# MCPGrundplatte16xOutput.net
KiCad netlist of a schematic drawn in EAGLE
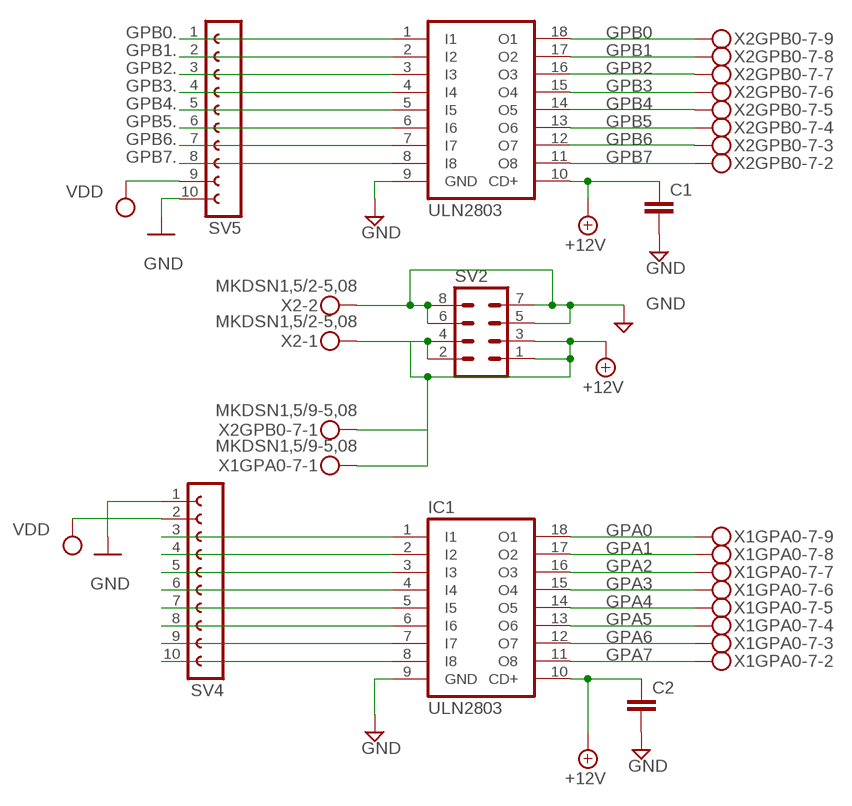
[diagram p0: schematic, sheet 1]

(export (version "E")
  (design (tool "Eeschema 10.0.6"))
  (components
    (comp (ref "C1")
      (value "C-EU025-024X044")
      (footprint "eagle-import:C025-024X044")
      (libsource (lib "eagle-import") (part "C-EU025-024X044"))
    )
    (comp (ref "C2")
      (value "C-EU025-024X044")
      (footprint "eagle-import:C025-024X044")
      (libsource (lib "eagle-import") (part "C-EU025-024X044"))
    )
    (comp (ref "IC1")
      (value "ULN2803")
      (footprint "eagle-import:DIL18")
      (libsource (lib "eagle-import") (part "ULN2803A"))
    )
    (comp (ref "IC4")
      (value "ULN2803")
      (footprint "eagle-import:DIL18")
      (libsource (lib "eagle-import") (part "ULN2803A"))
    )
    (comp (ref "SV2")
      (value "MA04-2")
      (footprint "eagle-import:MA04-2")
      (libsource (lib "eagle-import") (part "MA04-2"))
    )
    (comp (ref "SV4")
      (value "FE10-1")
      (footprint "eagle-import:FE10")
      (libsource (lib "eagle-import") (part "FE10-1"))
    )
    (comp (ref "SV5")
      (value "FE10-1")
      (footprint "eagle-import:FE10")
      (libsource (lib "eagle-import") (part "FE10-1"))
    )
    (comp (ref "X1GPA0-7")
      (value "MKDSN1,5/9-5,08")
      (footprint "eagle-import:MKDSN1,5_9-5,08")
      (libsource (lib "eagle-import") (part "MKDSN1,5/9-5,08"))
    )
    (comp (ref "X2")
      (value "MKDSN1,5/2-5,08")
      (footprint "eagle-import:MKDSN1,5_2-5,08")
      (libsource (lib "eagle-import") (part "MKDSN1,5/2-5,08"))
    )
    (comp (ref "X2GPB0-7")
      (value "MKDSN1,5/9-5,08")
      (footprint "eagle-import:MKDSN1,5_9-5,08")
      (libsource (lib "eagle-import") (part "MKDSN1,5/9-5,08"))
    )
  )
  (nets
    (net (code "1") (name "+12V") (class "Default")
      (node (ref "C1") (pin "1") (pinfunction "1_1") (pintype "passive"))
      (node (ref "C2") (pin "1") (pinfunction "1_1") (pintype "passive"))
      (node (ref "IC1") (pin "10") (pinfunction "CD+_10") (pintype "passive"))
      (node (ref "IC4") (pin "10") (pinfunction "CD+_10") (pintype "passive"))
      (node (ref "SV2") (pin "1") (pinfunction "1_1") (pintype "passive"))
      (node (ref "SV2") (pin "2") (pinfunction "2_2") (pintype "passive"))
      (node (ref "SV2") (pin "3") (pinfunction "3_3") (pintype "passive"))
      (node (ref "SV2") (pin "4") (pinfunction "4_4") (pintype "passive"))
      (node (ref "X1GPA0-7") (pin "1") (pinfunction "KL_1") (pintype "passive"))
      (node (ref "X2") (pin "1") (pinfunction "KL_1") (pintype "passive"))
      (node (ref "X2GPB0-7") (pin "1") (pinfunction "KL_1") (pintype "passive"))
    )
    (net (code "2") (name "/GPA0") (class "Default")
      (node (ref "IC1") (pin "18") (pinfunction "O1_18") (pintype "open_collector"))
      (node (ref "X1GPA0-7") (pin "9") (pinfunction "KL_9") (pintype "passive"))
    )
    (net (code "3") (name "/GPA1") (class "Default")
      (node (ref "IC1") (pin "17") (pinfunction "O2_17") (pintype "open_collector"))
      (node (ref "X1GPA0-7") (pin "8") (pinfunction "KL_8") (pintype "passive"))
    )
    (net (code "4") (name "/GPA2") (class "Default")
      (node (ref "IC1") (pin "16") (pinfunction "O3_16") (pintype "open_collector"))
      (node (ref "X1GPA0-7") (pin "7") (pinfunction "KL_7") (pintype "passive"))
    )
    (net (code "5") (name "/GPA3") (class "Default")
      (node (ref "IC1") (pin "15") (pinfunction "O4_15") (pintype "open_collector"))
      (node (ref "X1GPA0-7") (pin "6") (pinfunction "KL_6") (pintype "passive"))
    )
    (net (code "6") (name "/GPA4") (class "Default")
      (node (ref "IC1") (pin "14") (pinfunction "O5_14") (pintype "open_collector"))
      (node (ref "X1GPA0-7") (pin "5") (pinfunction "KL_5") (pintype "passive"))
    )
    (net (code "7") (name "/GPA5") (class "Default")
      (node (ref "IC1") (pin "13") (pinfunction "O6_13") (pintype "open_collector"))
      (node (ref "X1GPA0-7") (pin "4") (pinfunction "KL_4") (pintype "passive"))
    )
    (net (code "8") (name "/GPA6") (class "Default")
      (node (ref "IC1") (pin "12") (pinfunction "O7_12") (pintype "open_collector"))
      (node (ref "X1GPA0-7") (pin "3") (pinfunction "KL_3") (pintype "passive"))
    )
    (net (code "9") (name "/GPA7") (class "Default")
      (node (ref "IC1") (pin "11") (pinfunction "O8_11") (pintype "open_collector"))
      (node (ref "X1GPA0-7") (pin "2") (pinfunction "KL_2") (pintype "passive"))
    )
    (net (code "10") (name "/GPB0") (class "Default")
      (node (ref "IC4") (pin "18") (pinfunction "O1_18") (pintype "open_collector"))
      (node (ref "X2GPB0-7") (pin "9") (pinfunction "KL_9") (pintype "passive"))
    )
    (net (code "11") (name "/GPB0.") (class "Default")
      (node (ref "IC4") (pin "1") (pinfunction "I1_1") (pintype "input"))
      (node (ref "SV5") (pin "1") (pinfunction "1_1") (pintype "passive"))
    )
    (net (code "12") (name "/GPB1") (class "Default")
      (node (ref "IC4") (pin "17") (pinfunction "O2_17") (pintype "open_collector"))
      (node (ref "X2GPB0-7") (pin "8") (pinfunction "KL_8") (pintype "passive"))
    )
    (net (code "13") (name "/GPB1.") (class "Default")
      (node (ref "IC4") (pin "2") (pinfunction "I2_2") (pintype "input"))
      (node (ref "SV5") (pin "2") (pinfunction "2_2") (pintype "passive"))
    )
    (net (code "14") (name "/GPB2") (class "Default")
      (node (ref "IC4") (pin "16") (pinfunction "O3_16") (pintype "open_collector"))
      (node (ref "X2GPB0-7") (pin "7") (pinfunction "KL_7") (pintype "passive"))
    )
    (net (code "15") (name "/GPB2.") (class "Default")
      (node (ref "IC4") (pin "3") (pinfunction "I3_3") (pintype "input"))
      (node (ref "SV5") (pin "3") (pinfunction "3_3") (pintype "passive"))
    )
    (net (code "16") (name "/GPB3") (class "Default")
      (node (ref "IC4") (pin "15") (pinfunction "O4_15") (pintype "open_collector"))
      (node (ref "X2GPB0-7") (pin "6") (pinfunction "KL_6") (pintype "passive"))
    )
    (net (code "17") (name "/GPB3.") (class "Default")
      (node (ref "IC4") (pin "4") (pinfunction "I4_4") (pintype "input"))
      (node (ref "SV5") (pin "4") (pinfunction "4_4") (pintype "passive"))
    )
    (net (code "18") (name "/GPB4") (class "Default")
      (node (ref "IC4") (pin "14") (pinfunction "O5_14") (pintype "open_collector"))
      (node (ref "X2GPB0-7") (pin "5") (pinfunction "KL_5") (pintype "passive"))
    )
    (net (code "19") (name "/GPB4.") (class "Default")
      (node (ref "IC4") (pin "5") (pinfunction "I5_5") (pintype "input"))
      (node (ref "SV5") (pin "5") (pinfunction "5_5") (pintype "passive"))
    )
    (net (code "20") (name "/GPB5") (class "Default")
      (node (ref "IC4") (pin "13") (pinfunction "O6_13") (pintype "open_collector"))
      (node (ref "X2GPB0-7") (pin "4") (pinfunction "KL_4") (pintype "passive"))
    )
    (net (code "21") (name "/GPB5.") (class "Default")
      (node (ref "IC4") (pin "6") (pinfunction "I6_6") (pintype "input"))
      (node (ref "SV5") (pin "6") (pinfunction "6_6") (pintype "passive"))
    )
    (net (code "22") (name "/GPB6") (class "Default")
      (node (ref "IC4") (pin "12") (pinfunction "O7_12") (pintype "open_collector"))
      (node (ref "X2GPB0-7") (pin "3") (pinfunction "KL_3") (pintype "passive"))
    )
    (net (code "23") (name "/GPB6.") (class "Default")
      (node (ref "IC4") (pin "7") (pinfunction "I7_7") (pintype "input"))
      (node (ref "SV5") (pin "7") (pinfunction "7_7") (pintype "passive"))
    )
    (net (code "24") (name "/GPB7") (class "Default")
      (node (ref "IC4") (pin "11") (pinfunction "O8_11") (pintype "open_collector"))
      (node (ref "X2GPB0-7") (pin "2") (pinfunction "KL_2") (pintype "passive"))
    )
    (net (code "25") (name "/GPB7.") (class "Default")
      (node (ref "IC4") (pin "8") (pinfunction "I8_8") (pintype "input"))
      (node (ref "SV5") (pin "8") (pinfunction "8_8") (pintype "passive"))
    )
    (net (code "26") (name "GND") (class "Default")
      (node (ref "C1") (pin "2") (pinfunction "2_2") (pintype "passive"))
      (node (ref "C2") (pin "2") (pinfunction "2_2") (pintype "passive"))
      (node (ref "IC1") (pin "9") (pinfunction "GND_9") (pintype "power_in"))
      (node (ref "IC4") (pin "9") (pinfunction "GND_9") (pintype "power_in"))
      (node (ref "SV2") (pin "5") (pinfunction "5_5") (pintype "passive"))
      (node (ref "SV2") (pin "6") (pinfunction "6_6") (pintype "passive"))
      (node (ref "SV2") (pin "7") (pinfunction "7_7") (pintype "passive"))
      (node (ref "SV2") (pin "8") (pinfunction "8_8") (pintype "passive"))
      (node (ref "SV4") (pin "1") (pinfunction "1_1") (pintype "passive"))
      (node (ref "SV5") (pin "10") (pinfunction "10_10") (pintype "passive"))
      (node (ref "X2") (pin "2") (pinfunction "KL_2") (pintype "passive"))
    )
    (net (code "27") (name "Net-(IC1-I1)") (class "Default")
      (node (ref "IC1") (pin "1") (pinfunction "I1_1") (pintype "input"))
      (node (ref "SV4") (pin "3") (pinfunction "3_3") (pintype "passive"))
    )
    (net (code "28") (name "Net-(IC1-I2)") (class "Default")
      (node (ref "IC1") (pin "2") (pinfunction "I2_2") (pintype "input"))
      (node (ref "SV4") (pin "4") (pinfunction "4_4") (pintype "passive"))
    )
    (net (code "29") (name "Net-(IC1-I3)") (class "Default")
      (node (ref "IC1") (pin "3") (pinfunction "I3_3") (pintype "input"))
      (node (ref "SV4") (pin "5") (pinfunction "5_5") (pintype "passive"))
    )
    (net (code "30") (name "Net-(IC1-I4)") (class "Default")
      (node (ref "IC1") (pin "4") (pinfunction "I4_4") (pintype "input"))
      (node (ref "SV4") (pin "6") (pinfunction "6_6") (pintype "passive"))
    )
    (net (code "31") (name "Net-(IC1-I5)") (class "Default")
      (node (ref "IC1") (pin "5") (pinfunction "I5_5") (pintype "input"))
      (node (ref "SV4") (pin "7") (pinfunction "7_7") (pintype "passive"))
    )
    (net (code "32") (name "Net-(IC1-I6)") (class "Default")
      (node (ref "IC1") (pin "6") (pinfunction "I6_6") (pintype "input"))
      (node (ref "SV4") (pin "8") (pinfunction "8_8") (pintype "passive"))
    )
    (net (code "33") (name "Net-(IC1-I7)") (class "Default")
      (node (ref "IC1") (pin "7") (pinfunction "I7_7") (pintype "input"))
      (node (ref "SV4") (pin "9") (pinfunction "9_9") (pintype "passive"))
    )
    (net (code "34") (name "Net-(IC1-I8)") (class "Default")
      (node (ref "IC1") (pin "8") (pinfunction "I8_8") (pintype "input"))
      (node (ref "SV4") (pin "10") (pinfunction "10_10") (pintype "passive"))
    )
    (net (code "35") (name "VDD") (class "Default")
      (node (ref "SV4") (pin "2") (pinfunction "2_2") (pintype "passive"))
      (node (ref "SV5") (pin "9") (pinfunction "9_9") (pintype "passive"))
    )
  )
)
